# BACKUP_POWER_2.net
KiCad netlist of a schematic drawn in Altium Designer
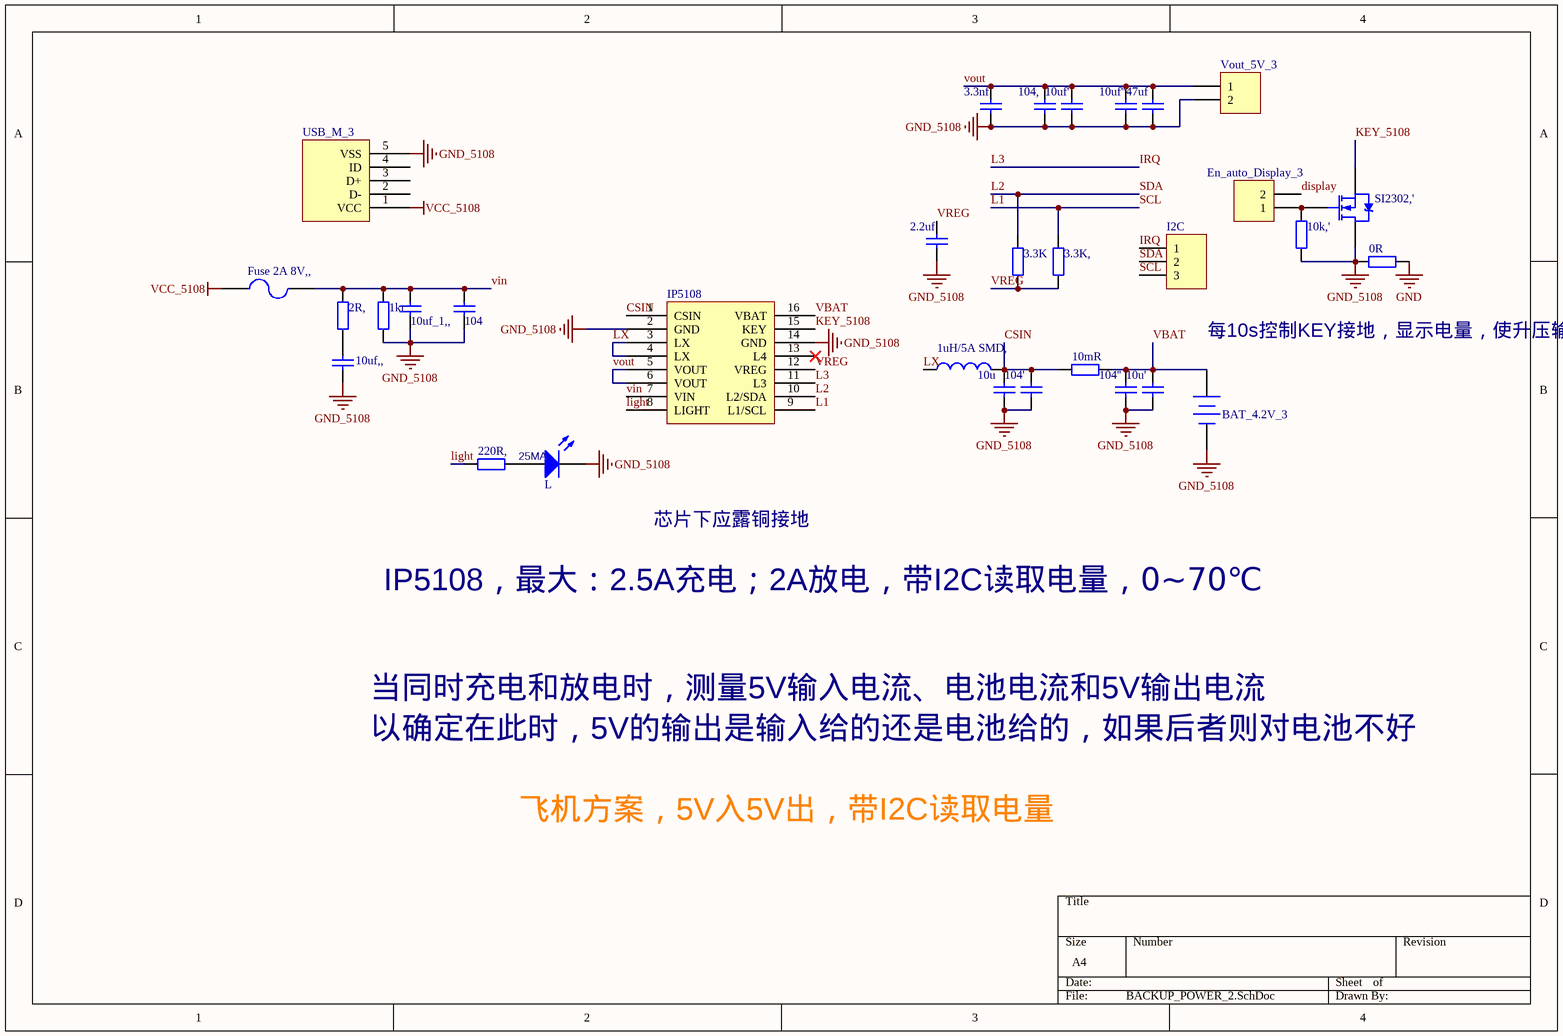
[diagram p0: BACKUP_POWER_2.SchDoc]

(export (version "E")
  (design (tool "Eeschema 10.0.6"))
  (components
    (comp (ref "0R")
      (value "Res2")
      (footprint "0805A")
      (description "Resistor")
      (fields (field (name "PUBLISHER") "Altium Limited"))
      (libsource (lib "Miscellaneous Devices") (part "Res2"))
    )
    (comp (ref "1kr")
      (value "Res2")
      (footprint "0805A")
      (description "Resistor")
      (fields (field (name "PUBLISHER") "Altium Limited"))
      (libsource (lib "") (part "Res2_1"))
    )
    (comp (ref "1uH/5A SMD,")
      (value "Inductor")
      (footprint "6 X 6-L")
      (fields (field (name "PUBLISHER") "Altium Limited"))
      (libsource (lib "Miscellaneous Devices") (part "Inductor"))
    )
    (comp (ref "2.2uf")
      (value "Cap")
      (footprint "C-RAD-0805")
      (description "Capacitor")
      (fields (field (name "PUBLISHER") "Altium Limited"))
      (libsource (lib "Miscellaneous Devices") (part "Cap"))
    )
    (comp (ref "2R,")
      (value "Res2")
      (footprint "0805A")
      (description "Resistor")
      (fields (field (name "PUBLISHER") "Altium Limited"))
      (libsource (lib "") (part "Res2_1"))
    )
    (comp (ref "3.3K")
      (value "Res2")
      (footprint "0805A")
      (description "Resistor")
      (fields (field (name "PUBLISHER") "Altium Limited"))
      (libsource (lib "") (part "Res2_1"))
    )
    (comp (ref "3.3K,")
      (value "Res2")
      (footprint "0805A")
      (description "Resistor")
      (fields (field (name "PUBLISHER") "Altium Limited"))
      (libsource (lib "") (part "Res2_1"))
    )
    (comp (ref "3.3nf")
      (value "Cap")
      (footprint "C-RAD-0805")
      (description "Capacitor")
      (fields (field (name "PUBLISHER") "Altium Limited"))
      (libsource (lib "Miscellaneous Devices") (part "Cap"))
    )
    (comp (ref "10k,'")
      (value "Res2")
      (footprint "0805A")
      (description "Resistor")
      (fields (field (name "PUBLISHER") "Altium Limited"))
      (libsource (lib "") (part "Res2_2"))
    )
    (comp (ref "10mR")
      (value "Res2")
      (footprint "1206R")
      (description "Resistor")
      (fields (field (name "PUBLISHER") "Altium Limited"))
      (libsource (lib "") (part "Res2_3"))
    )
    (comp (ref "10u")
      (value "Cap")
      (footprint "C-RAD-0805")
      (description "Capacitor")
      (fields (field (name "PUBLISHER") "Altium Limited"))
      (libsource (lib "Miscellaneous Devices") (part "Cap"))
    )
    (comp (ref "10u'")
      (value "Cap")
      (footprint "C-RAD-0805")
      (description "Capacitor")
      (fields (field (name "PUBLISHER") "Altium Limited"))
      (libsource (lib "Miscellaneous Devices") (part "Cap"))
    )
    (comp (ref "10uf'")
      (value "Cap")
      (footprint "C-RAD-0805")
      (description "Capacitor")
      (fields (field (name "PUBLISHER") "Altium Limited"))
      (libsource (lib "Miscellaneous Devices") (part "Cap"))
    )
    (comp (ref "10uf''")
      (value "Cap")
      (footprint "C-RAD-0805")
      (description "Capacitor")
      (fields (field (name "PUBLISHER") "Altium Limited"))
      (libsource (lib "Miscellaneous Devices") (part "Cap"))
    )
    (comp (ref "10uf,,")
      (value "Cap")
      (footprint "C-RAD-0805")
      (description "Capacitor")
      (fields (field (name "PUBLISHER") "Altium Limited"))
      (libsource (lib "Miscellaneous Devices") (part "Cap"))
    )
    (comp (ref "10uf_1,,")
      (value "Cap")
      (footprint "C-RAD-0805")
      (description "Capacitor")
      (fields (field (name "PUBLISHER") "Altium Limited"))
      (libsource (lib "Miscellaneous Devices") (part "Cap"))
    )
    (comp (ref "47uf")
      (value "Cap")
      (footprint "C-RAD-0805")
      (description "Capacitor")
      (fields (field (name "PUBLISHER") "Altium Limited"))
      (libsource (lib "Miscellaneous Devices") (part "Cap"))
    )
    (comp (ref "104")
      (value "Cap")
      (footprint "C-RAD-0805")
      (description "Capacitor")
      (fields (field (name "PUBLISHER") "Altium Limited"))
      (libsource (lib "Miscellaneous Devices") (part "Cap"))
    )
    (comp (ref "104'")
      (value "Cap")
      (footprint "C-RAD-0805")
      (description "Capacitor")
      (fields (field (name "PUBLISHER") "Altium Limited"))
      (libsource (lib "Miscellaneous Devices") (part "Cap"))
    )
    (comp (ref "104''")
      (value "Cap")
      (footprint "C-RAD-0805")
      (description "Capacitor")
      (fields (field (name "PUBLISHER") "Altium Limited"))
      (libsource (lib "Miscellaneous Devices") (part "Cap"))
    )
    (comp (ref "104,")
      (value "Cap")
      (footprint "C-RAD-0805")
      (description "Capacitor")
      (fields (field (name "PUBLISHER") "Altium Limited"))
      (libsource (lib "Miscellaneous Devices") (part "Cap"))
    )
    (comp (ref "220R,")
      (value "Res2")
      (footprint "0805A")
      (description "Resistor")
      (fields (field (name "PUBLISHER") "Altium Limited"))
      (libsource (lib "Miscellaneous Devices") (part "Res2"))
    )
    (comp (ref "BAT_4.2V_3") (value "B") (footprint "HDR1X2") (libsource (lib "原理图封装库") (part "BAT")))
    (comp (ref "En_auto_Display_3")
      (value "Header 2")
      (footprint "HDR1X2")
      (description "Header, 2-Pin")
      (fields (field (name "PUBLISHER") "Altium Limited"))
      (libsource (lib "") (part "Header 2_1"))
    )
    (comp (ref "Fuse 2A 8V,,")
      (value "Fuse 2")
      (footprint "1812F")
      (description "Fuse")
      (fields (field (name "PUBLISHER") "Altium Limited"))
      (libsource (lib "Miscellaneous Devices") (part "Fuse 2"))
    )
    (comp (ref "I2C")
      (value "Header 3")
      (footprint "HDR1X3")
      (description "Header, 3-Pin")
      (fields (field (name "PUBLISHER") "Altium Limited"))
      (libsource (lib "Miscellaneous Connectors") (part "Header 3"))
    )
    (comp (ref "IP5108") (value "~") (footprint "SOP16") (libsource (lib "电源管理") (part "IP5108")))
    (comp (ref "L")
      (value "LED0")
      (footprint "LED_0805")
      (description "发光二极管")
      (fields (field (name "PUBLISHER") "Altium Limited"))
      (libsource (lib "Fszhang") (part "LED0"))
    )
    (comp (ref "SI2302,'")
      (value "LR7843")
      (footprint "SOT-23")
      (description "N-Channel Power MOSFET")
      (fields (field (name "PUBLISHER") "Altium Limited"))
      (libsource (lib "Miscellaneous Devices") (part "NMOS-2"))
    )
    (comp (ref "USB_M_3")
      (value "USB_M")
      (footprint "USB_MICRO")
      (description "MicroUSB接口")
      (libsource (lib "Fszhang") (part "USB_M"))
    )
    (comp (ref "Vout_5V_3")
      (value "Header 2")
      (footprint "HDR1X2")
      (description "Header, 2-Pin")
      (fields (field (name "PUBLISHER") "Altium Limited"))
      (libsource (lib "Miscellaneous Connectors") (part "Header 2"))
    )
  )
  (nets
    (net (code "1") (name "/CSIN") (class "Default")
      (node (ref "104'") (pin "1") (pinfunction "1_1") (pintype "passive"))
      (node (ref "10mR") (pin "1") (pinfunction "1_1") (pintype "passive"))
      (node (ref "10u") (pin "1") (pinfunction "1_1") (pintype "passive"))
      (node (ref "1uH/5A SMD,") (pin "2") (pinfunction "2_2") (pintype "passive"))
      (node (ref "IP5108") (pin "1") (pinfunction "CSIN_1") (pintype "passive"))
    )
    (net (code "2") (name "/IRQ") (class "Default")
      (node (ref "I2C") (pin "1") (pinfunction "1_1") (pintype "passive"))
      (node (ref "IP5108") (pin "11") (pinfunction "L3_11") (pintype "passive"))
    )
    (net (code "3") (name "/KEY_5108") (class "Default")
      (node (ref "IP5108") (pin "15") (pinfunction "KEY_15") (pintype "passive"))
      (node (ref "SI2302,'") (pin "3") (pinfunction "S_3") (pintype "passive"))
    )
    (net (code "4") (name "/L1") (class "Default")
      (node (ref "3.3K,") (pin "2") (pinfunction "2_2") (pintype "passive"))
      (node (ref "I2C") (pin "3") (pinfunction "3_3") (pintype "passive"))
      (node (ref "IP5108") (pin "9") (pinfunction "L1/SCL_9") (pintype "passive"))
    )
    (net (code "5") (name "/L2") (class "Default")
      (node (ref "3.3K") (pin "2") (pinfunction "2_2") (pintype "passive"))
      (node (ref "I2C") (pin "2") (pinfunction "2_2") (pintype "passive"))
      (node (ref "IP5108") (pin "10") (pinfunction "L2/SDA_10") (pintype "passive"))
    )
    (net (code "6") (name "/LX") (class "Default")
      (node (ref "1uH/5A SMD,") (pin "1") (pinfunction "1_1") (pintype "passive"))
      (node (ref "IP5108") (pin "3") (pinfunction "LX_3") (pintype "passive"))
      (node (ref "IP5108") (pin "4") (pinfunction "LX_4") (pintype "passive"))
    )
    (net (code "7") (name "/VBAT") (class "Default")
      (node (ref "104''") (pin "1") (pinfunction "1_1") (pintype "passive"))
      (node (ref "10mR") (pin "2") (pinfunction "2_2") (pintype "passive"))
      (node (ref "10u'") (pin "1") (pinfunction "1_1") (pintype "passive"))
      (node (ref "BAT_4.2V_3") (pin "1") (pinfunction "+_1") (pintype "passive"))
      (node (ref "IP5108") (pin "16") (pinfunction "VBAT_16") (pintype "passive"))
    )
    (net (code "8") (name "/VREG") (class "Default")
      (node (ref "2.2uf") (pin "2") (pinfunction "2_2") (pintype "passive"))
      (node (ref "3.3K") (pin "1") (pinfunction "1_1") (pintype "passive"))
      (node (ref "3.3K,") (pin "1") (pinfunction "1_1") (pintype "passive"))
      (node (ref "IP5108") (pin "12") (pinfunction "VREG_12") (pintype "passive"))
    )
    (net (code "9") (name "/display") (class "Default")
      (node (ref "En_auto_Display_3") (pin "2") (pinfunction "2_2") (pintype "passive"))
    )
    (net (code "10") (name "/light") (class "Default")
      (node (ref "220R,") (pin "2") (pinfunction "2_2") (pintype "passive"))
      (node (ref "IP5108") (pin "8") (pinfunction "LIGHT_8") (pintype "passive"))
    )
    (net (code "11") (name "/vin") (class "Default")
      (node (ref "104") (pin "1") (pinfunction "1_1") (pintype "passive"))
      (node (ref "10uf_1,,") (pin "1") (pinfunction "1_1") (pintype "passive"))
      (node (ref "1kr") (pin "2") (pinfunction "2_2") (pintype "passive"))
      (node (ref "2R,") (pin "2") (pinfunction "2_2") (pintype "passive"))
      (node (ref "Fuse 2A 8V,,") (pin "2") (pinfunction "2_2") (pintype "passive"))
      (node (ref "IP5108") (pin "7") (pinfunction "VIN_7") (pintype "passive"))
    )
    (net (code "12") (name "/vout") (class "Default")
      (node (ref "104,") (pin "1") (pinfunction "1_1") (pintype "passive"))
      (node (ref "10uf'") (pin "1") (pinfunction "1_1") (pintype "passive"))
      (node (ref "10uf''") (pin "1") (pinfunction "1_1") (pintype "passive"))
      (node (ref "3.3nf") (pin "2") (pinfunction "2_2") (pintype "passive"))
      (node (ref "47uf") (pin "1") (pinfunction "1_1") (pintype "passive"))
      (node (ref "IP5108") (pin "5") (pinfunction "VOUT_5") (pintype "passive"))
      (node (ref "IP5108") (pin "6") (pinfunction "VOUT_6") (pintype "passive"))
      (node (ref "Vout_5V_3") (pin "1") (pinfunction "1_1") (pintype "passive"))
    )
    (net (code "13") (name "GND") (class "Default")
      (node (ref "0R") (pin "1") (pinfunction "1_1") (pintype "passive"))
    )
    (net (code "14") (name "GND_5108") (class "Default")
      (node (ref "0R") (pin "2") (pinfunction "2_2") (pintype "passive"))
      (node (ref "104") (pin "2") (pinfunction "2_2") (pintype "passive"))
      (node (ref "104'") (pin "2") (pinfunction "2_2") (pintype "passive"))
      (node (ref "104''") (pin "2") (pinfunction "2_2") (pintype "passive"))
      (node (ref "104,") (pin "2") (pinfunction "2_2") (pintype "passive"))
      (node (ref "10k,'") (pin "2") (pinfunction "2_2") (pintype "passive"))
      (node (ref "10u") (pin "2") (pinfunction "2_2") (pintype "passive"))
      (node (ref "10u'") (pin "2") (pinfunction "2_2") (pintype "passive"))
      (node (ref "10uf'") (pin "2") (pinfunction "2_2") (pintype "passive"))
      (node (ref "10uf''") (pin "2") (pinfunction "2_2") (pintype "passive"))
      (node (ref "10uf,,") (pin "2") (pinfunction "2_2") (pintype "passive"))
      (node (ref "10uf_1,,") (pin "2") (pinfunction "2_2") (pintype "passive"))
      (node (ref "1kr") (pin "1") (pinfunction "1_1") (pintype "passive"))
      (node (ref "2.2uf") (pin "1") (pinfunction "1_1") (pintype "passive"))
      (node (ref "3.3nf") (pin "1") (pinfunction "1_1") (pintype "passive"))
      (node (ref "47uf") (pin "2") (pinfunction "2_2") (pintype "passive"))
      (node (ref "BAT_4.2V_3") (pin "2") (pinfunction "-_2") (pintype "passive"))
      (node (ref "IP5108") (pin "14") (pinfunction "GND_14") (pintype "passive"))
      (node (ref "IP5108") (pin "2") (pinfunction "GND_2") (pintype "passive"))
      (node (ref "L") (pin "2") (pinfunction "K_2") (pintype "passive"))
      (node (ref "SI2302,'") (pin "2") (pinfunction "D_2") (pintype "passive"))
      (node (ref "USB_M_3") (pin "5") (pinfunction "VSS_5") (pintype "passive"))
      (node (ref "Vout_5V_3") (pin "2") (pinfunction "2_2") (pintype "passive"))
    )
    (net (code "15") (name "Net-(10uf,,-Pad1)") (class "Default")
      (node (ref "10uf,,") (pin "1") (pinfunction "1_1") (pintype "passive"))
      (node (ref "2R,") (pin "1") (pinfunction "1_1") (pintype "passive"))
    )
    (net (code "16") (name "Net-(L-A)") (class "Default")
      (node (ref "220R,") (pin "1") (pinfunction "1_1") (pintype "passive"))
      (node (ref "L") (pin "1") (pinfunction "A_1") (pintype "passive"))
    )
    (net (code "17") (name "Net-(SI2302,'-G)") (class "Default")
      (node (ref "10k,'") (pin "1") (pinfunction "1_1") (pintype "passive"))
      (node (ref "En_auto_Display_3") (pin "1") (pinfunction "1_1") (pintype "passive"))
      (node (ref "SI2302,'") (pin "1") (pinfunction "G_1") (pintype "passive"))
    )
    (net (code "18") (name "VCC_5108") (class "Default")
      (node (ref "Fuse 2A 8V,,") (pin "1") (pinfunction "1_1") (pintype "passive"))
      (node (ref "USB_M_3") (pin "1") (pinfunction "VCC_1") (pintype "passive"))
    )
    (net (code "19") (name "unconnected-(IP5108-L4-Pad13)") (class "Default")
      (node (ref "IP5108") (pin "13") (pinfunction "L4_13") (pintype "passive+no_connect"))
    )
    (net (code "20") (name "unconnected-(USB_M_3-D+-Pad3)") (class "Default")
      (node (ref "USB_M_3") (pin "3") (pinfunction "D+_3") (pintype "passive"))
    )
    (net (code "21") (name "unconnected-(USB_M_3-D--Pad2)") (class "Default")
      (node (ref "USB_M_3") (pin "2") (pinfunction "D-_2") (pintype "passive"))
    )
    (net (code "22") (name "unconnected-(USB_M_3-ID-Pad4)") (class "Default")
      (node (ref "USB_M_3") (pin "4") (pinfunction "ID_4") (pintype "passive"))
    )
  )
)
